# ATmega328P.net
KiCad netlist of a schematic drawn in EAGLE
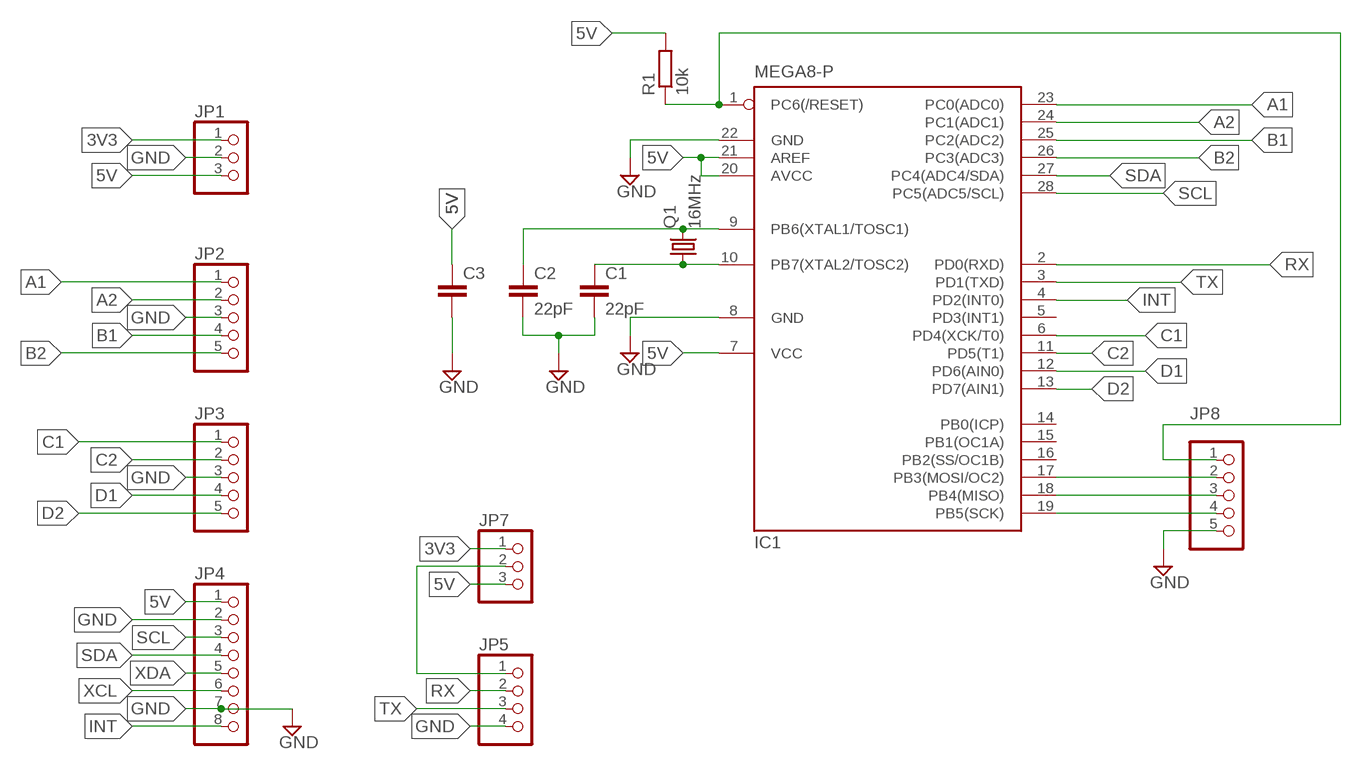
[diagram p0: schematic, sheet 1]

(export (version "E")
  (design (tool "Eeschema 10.0.6"))
  (components
    (comp (ref "C1")
      (value "22pF")
      (footprint "eagle-import:C2.5-2")
      (libsource (lib "eagle-import") (part "C2.5/2"))
    )
    (comp (ref "C2")
      (value "22pF")
      (footprint "eagle-import:C2.5-2")
      (libsource (lib "eagle-import") (part "C2.5/2"))
    )
    (comp (ref "C3")
      (value "C2.5/2")
      (footprint "eagle-import:C2.5-2")
      (libsource (lib "eagle-import") (part "C2.5/2"))
    )
    (comp (ref "IC1")
      (value "MEGA8-P")
      (footprint "eagle-import:DIL28-3")
      (libsource (lib "eagle-import") (part "MEGA8-P"))
    )
    (comp (ref "JP1")
      (value "PINHD-1X3/90")
      (footprint "eagle-import:1X03_90")
      (libsource (lib "eagle-import") (part "PINHD-1X3/90"))
    )
    (comp (ref "JP2")
      (value "PINHD-1X5/90")
      (footprint "eagle-import:1X05_90")
      (libsource (lib "eagle-import") (part "PINHD-1X5/90"))
    )
    (comp (ref "JP3")
      (value "PINHD-1X5/90")
      (footprint "eagle-import:1X05_90")
      (libsource (lib "eagle-import") (part "PINHD-1X5/90"))
    )
    (comp (ref "JP4")
      (value "PINHD-1X8/90")
      (footprint "eagle-import:1X08_90")
      (libsource (lib "eagle-import") (part "PINHD-1X8/90"))
    )
    (comp (ref "JP5")
      (value "PINHD-1X4/90")
      (footprint "eagle-import:1X04_90")
      (libsource (lib "eagle-import") (part "PINHD-1X4/90"))
    )
    (comp (ref "JP7")
      (value "PINHD-1X3")
      (footprint "eagle-import:1X03")
      (libsource (lib "eagle-import") (part "PINHD-1X3"))
    )
    (comp (ref "JP8")
      (value "PINHD-1X5")
      (footprint "eagle-import:1X05")
      (libsource (lib "eagle-import") (part "PINHD-1X5"))
    )
    (comp (ref "Q1")
      (value "16MHz")
      (footprint "eagle-import:HC49_S")
      (libsource (lib "eagle-import") (part "CRYSTALHC49S"))
    )
    (comp (ref "R1")
      (value "10k")
      (footprint "eagle-import:0207_10")
      (libsource (lib "eagle-import") (part "R-EU_0207/10"))
    )
  )
  (nets
    (net (code "1") (name "3V3") (class "Default")
      (node (ref "JP1") (pin "1") (pinfunction "1_1") (pintype "passive"))
      (node (ref "JP7") (pin "1") (pinfunction "1_1") (pintype "passive"))
    )
    (net (code "2") (name "5V") (class "Default")
      (node (ref "C3") (pin "1") (pinfunction "1_1") (pintype "passive"))
      (node (ref "IC1") (pin "20") (pinfunction "AVCC_20") (pintype "power_in"))
      (node (ref "IC1") (pin "21") (pinfunction "AREF_21") (pintype "passive"))
      (node (ref "IC1") (pin "7") (pinfunction "VCC_7") (pintype "power_in"))
      (node (ref "JP1") (pin "3") (pinfunction "3_3") (pintype "passive"))
      (node (ref "JP4") (pin "1") (pinfunction "1_1") (pintype "passive"))
      (node (ref "JP7") (pin "3") (pinfunction "3_3") (pintype "passive"))
      (node (ref "R1") (pin "2") (pinfunction "2_2") (pintype "passive"))
    )
    (net (code "3") (name "A1") (class "Default")
      (node (ref "IC1") (pin "23") (pinfunction "PC0(ADC0)_23") (pintype "bidirectional"))
      (node (ref "JP2") (pin "1") (pinfunction "1_1") (pintype "passive"))
    )
    (net (code "4") (name "A2") (class "Default")
      (node (ref "IC1") (pin "24") (pinfunction "PC1(ADC1)_24") (pintype "bidirectional"))
      (node (ref "JP2") (pin "2") (pinfunction "2_2") (pintype "passive"))
    )
    (net (code "5") (name "B1") (class "Default")
      (node (ref "IC1") (pin "25") (pinfunction "PC2(ADC2)_25") (pintype "bidirectional"))
      (node (ref "JP2") (pin "4") (pinfunction "4_4") (pintype "passive"))
    )
    (net (code "6") (name "B2") (class "Default")
      (node (ref "IC1") (pin "26") (pinfunction "PC3(ADC3)_26") (pintype "bidirectional"))
      (node (ref "JP2") (pin "5") (pinfunction "5_5") (pintype "passive"))
    )
    (net (code "7") (name "C1") (class "Default")
      (node (ref "IC1") (pin "6") (pinfunction "PD4(XCK/T0)_6") (pintype "bidirectional"))
      (node (ref "JP3") (pin "1") (pinfunction "1_1") (pintype "passive"))
    )
    (net (code "8") (name "C2") (class "Default")
      (node (ref "IC1") (pin "11") (pinfunction "PD5(T1)_11") (pintype "bidirectional"))
      (node (ref "JP3") (pin "2") (pinfunction "2_2") (pintype "passive"))
    )
    (net (code "9") (name "D1") (class "Default")
      (node (ref "IC1") (pin "12") (pinfunction "PD6(AIN0)_12") (pintype "bidirectional"))
      (node (ref "JP3") (pin "4") (pinfunction "4_4") (pintype "passive"))
    )
    (net (code "10") (name "D2") (class "Default")
      (node (ref "IC1") (pin "13") (pinfunction "PD7(AIN1)_13") (pintype "bidirectional"))
      (node (ref "JP3") (pin "5") (pinfunction "5_5") (pintype "passive"))
    )
    (net (code "11") (name "GND") (class "Default")
      (node (ref "C1") (pin "2") (pinfunction "2_2") (pintype "passive"))
      (node (ref "C2") (pin "2") (pinfunction "2_2") (pintype "passive"))
      (node (ref "C3") (pin "2") (pinfunction "2_2") (pintype "passive"))
      (node (ref "IC1") (pin "22") (pinfunction "GND_22") (pintype "power_in"))
      (node (ref "IC1") (pin "8") (pinfunction "GND_8") (pintype "power_in"))
      (node (ref "JP1") (pin "2") (pinfunction "2_2") (pintype "passive"))
      (node (ref "JP2") (pin "3") (pinfunction "3_3") (pintype "passive"))
      (node (ref "JP3") (pin "3") (pinfunction "3_3") (pintype "passive"))
      (node (ref "JP4") (pin "2") (pinfunction "2_2") (pintype "passive"))
      (node (ref "JP4") (pin "7") (pinfunction "7_7") (pintype "passive"))
      (node (ref "JP5") (pin "4") (pinfunction "4_4") (pintype "passive"))
      (node (ref "JP8") (pin "5") (pinfunction "5_5") (pintype "passive"))
    )
    (net (code "12") (name "INT") (class "Default")
      (node (ref "IC1") (pin "4") (pinfunction "PD2(INT0)_4") (pintype "bidirectional"))
      (node (ref "JP4") (pin "8") (pinfunction "8_8") (pintype "passive"))
    )
    (net (code "13") (name "Net-(IC1-PB3(MOSI{slash}OC2))") (class "Default")
      (node (ref "IC1") (pin "17") (pinfunction "PB3(MOSI/OC2)_17") (pintype "bidirectional"))
      (node (ref "JP8") (pin "2") (pinfunction "2_2") (pintype "passive"))
    )
    (net (code "14") (name "Net-(IC1-PB4(MISO))") (class "Default")
      (node (ref "IC1") (pin "18") (pinfunction "PB4(MISO)_18") (pintype "bidirectional"))
      (node (ref "JP8") (pin "3") (pinfunction "3_3") (pintype "passive"))
    )
    (net (code "15") (name "Net-(IC1-PB5(SCK))") (class "Default")
      (node (ref "IC1") (pin "19") (pinfunction "PB5(SCK)_19") (pintype "bidirectional"))
      (node (ref "JP8") (pin "4") (pinfunction "4_4") (pintype "passive"))
    )
    (net (code "16") (name "Net-(IC1-PB6(XTAL1{slash}TOSC1))") (class "Default")
      (node (ref "C2") (pin "1") (pinfunction "1_1") (pintype "passive"))
      (node (ref "IC1") (pin "9") (pinfunction "PB6(XTAL1/TOSC1)_9") (pintype "bidirectional"))
      (node (ref "Q1") (pin "2") (pinfunction "2_2") (pintype "passive"))
    )
    (net (code "17") (name "Net-(IC1-PB7(XTAL2{slash}TOSC2))") (class "Default")
      (node (ref "C1") (pin "1") (pinfunction "1_1") (pintype "passive"))
      (node (ref "IC1") (pin "10") (pinfunction "PB7(XTAL2/TOSC2)_10") (pintype "bidirectional"))
      (node (ref "Q1") (pin "1") (pinfunction "1_1") (pintype "passive"))
    )
    (net (code "18") (name "Net-(IC1-PC6({slash}RESET))") (class "Default")
      (node (ref "IC1") (pin "1") (pinfunction "PC6(/RESET)_1") (pintype "bidirectional"))
      (node (ref "JP8") (pin "1") (pinfunction "1_1") (pintype "passive"))
      (node (ref "R1") (pin "1") (pinfunction "1_1") (pintype "passive"))
    )
    (net (code "19") (name "Net-(JP5-Pad1)") (class "Default")
      (node (ref "JP5") (pin "1") (pinfunction "1_1") (pintype "passive"))
      (node (ref "JP7") (pin "2") (pinfunction "2_2") (pintype "passive"))
    )
    (net (code "20") (name "RX") (class "Default")
      (node (ref "IC1") (pin "2") (pinfunction "PD0(RXD)_2") (pintype "bidirectional"))
      (node (ref "JP5") (pin "2") (pinfunction "2_2") (pintype "passive"))
    )
    (net (code "21") (name "SCL") (class "Default")
      (node (ref "IC1") (pin "28") (pinfunction "PC5(ADC5/SCL)_28") (pintype "bidirectional"))
      (node (ref "JP4") (pin "3") (pinfunction "3_3") (pintype "passive"))
    )
    (net (code "22") (name "SDA") (class "Default")
      (node (ref "IC1") (pin "27") (pinfunction "PC4(ADC4/SDA)_27") (pintype "bidirectional"))
      (node (ref "JP4") (pin "4") (pinfunction "4_4") (pintype "passive"))
    )
    (net (code "23") (name "TX") (class "Default")
      (node (ref "IC1") (pin "3") (pinfunction "PD1(TXD)_3") (pintype "bidirectional"))
      (node (ref "JP5") (pin "3") (pinfunction "3_3") (pintype "passive"))
    )
    (net (code "24") (name "XCL") (class "Default")
      (node (ref "JP4") (pin "6") (pinfunction "6_6") (pintype "passive"))
    )
    (net (code "25") (name "XDA") (class "Default")
      (node (ref "JP4") (pin "5") (pinfunction "5_5") (pintype "passive"))
    )
    (net (code "26") (name "unconnected-(IC1-PB0(ICP)-Pad14)") (class "Default")
      (node (ref "IC1") (pin "14") (pinfunction "PB0(ICP)_14") (pintype "bidirectional"))
    )
    (net (code "27") (name "unconnected-(IC1-PB1(OC1A)-Pad15)") (class "Default")
      (node (ref "IC1") (pin "15") (pinfunction "PB1(OC1A)_15") (pintype "bidirectional"))
    )
    (net (code "28") (name "unconnected-(IC1-PB2(SS{slash}OC1B)-Pad16)") (class "Default")
      (node (ref "IC1") (pin "16") (pinfunction "PB2(SS/OC1B)_16") (pintype "bidirectional"))
    )
    (net (code "29") (name "unconnected-(IC1-PD3(INT1)-Pad5)") (class "Default")
      (node (ref "IC1") (pin "5") (pinfunction "PD3(INT1)_5") (pintype "bidirectional"))
    )
  )
)
